# ProPrj_Syntheseproject_2025-2026_2025-11.net
KiCad netlist of a schematic drawn in EasyEDA Pro
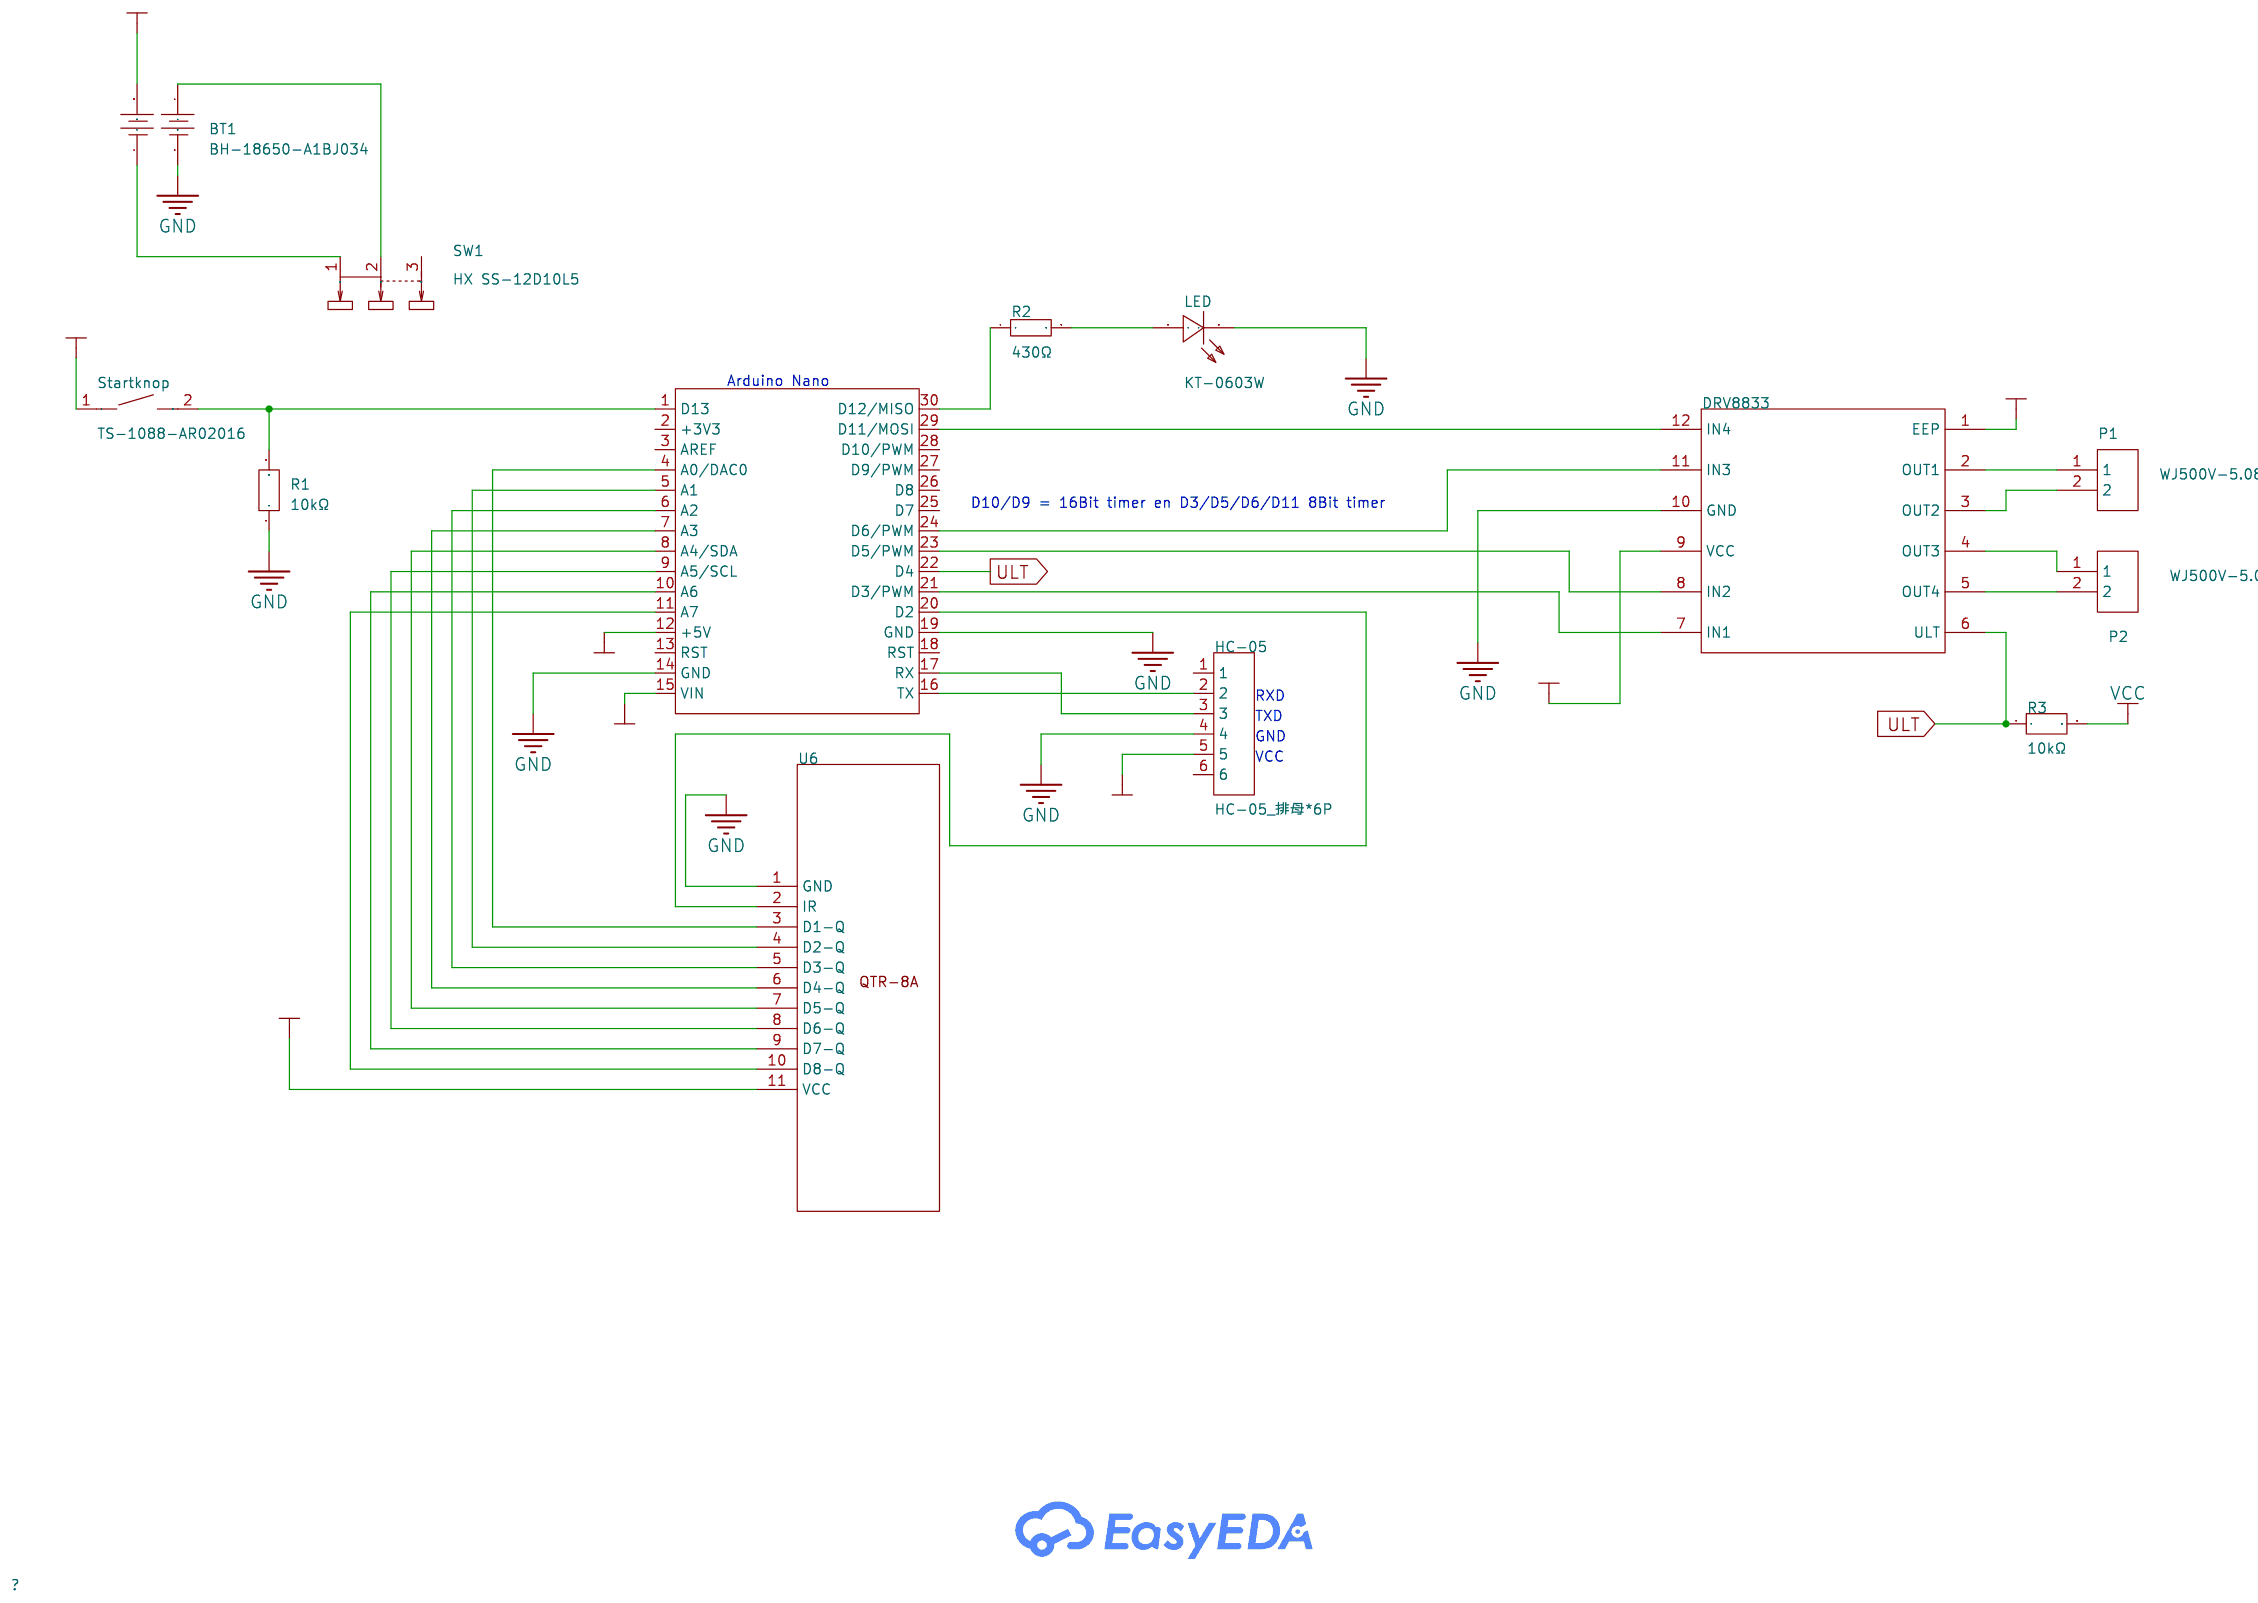
[diagram p0: Totaal]
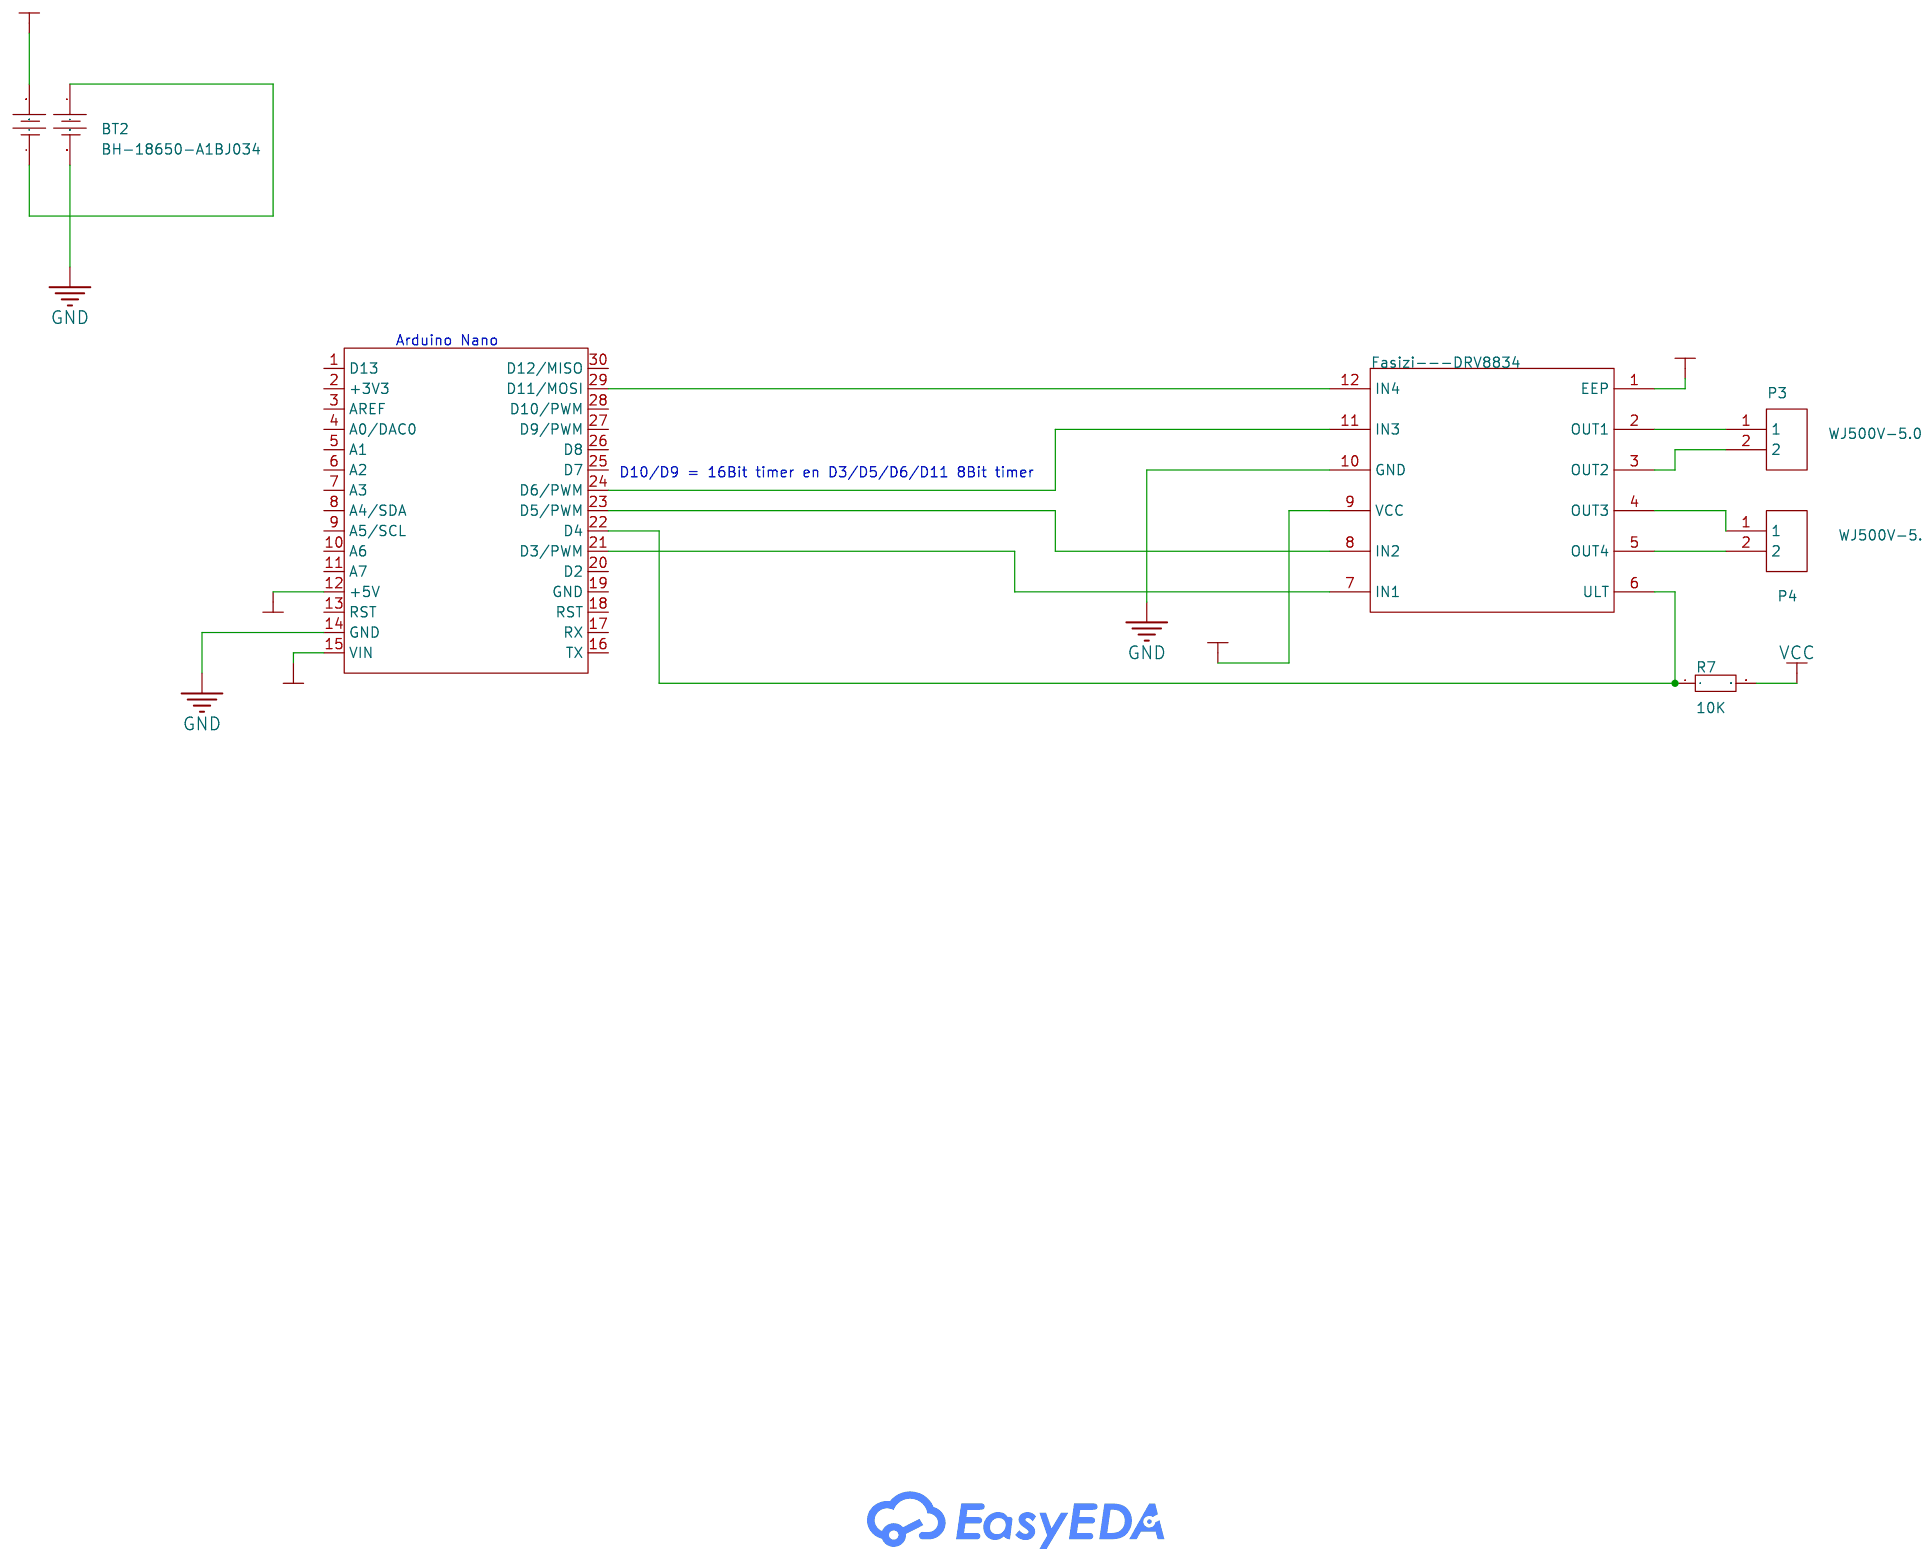
[diagram p1: Deelschema-Drive]
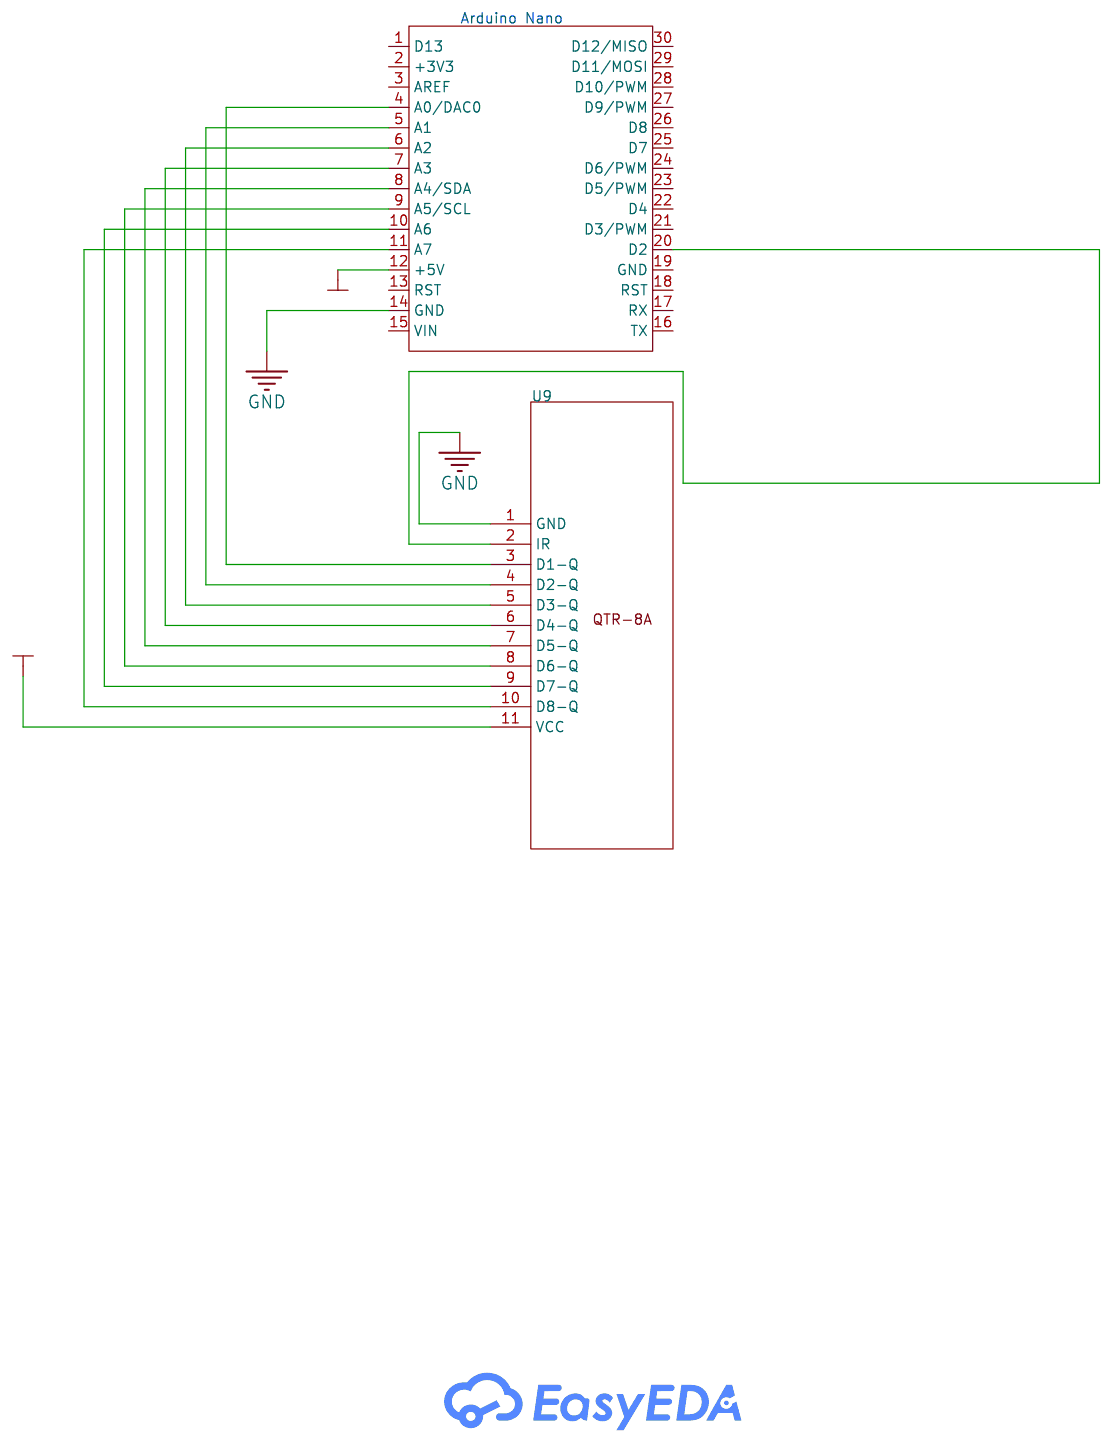
[diagram p2: Deelschema-QTR-8A]
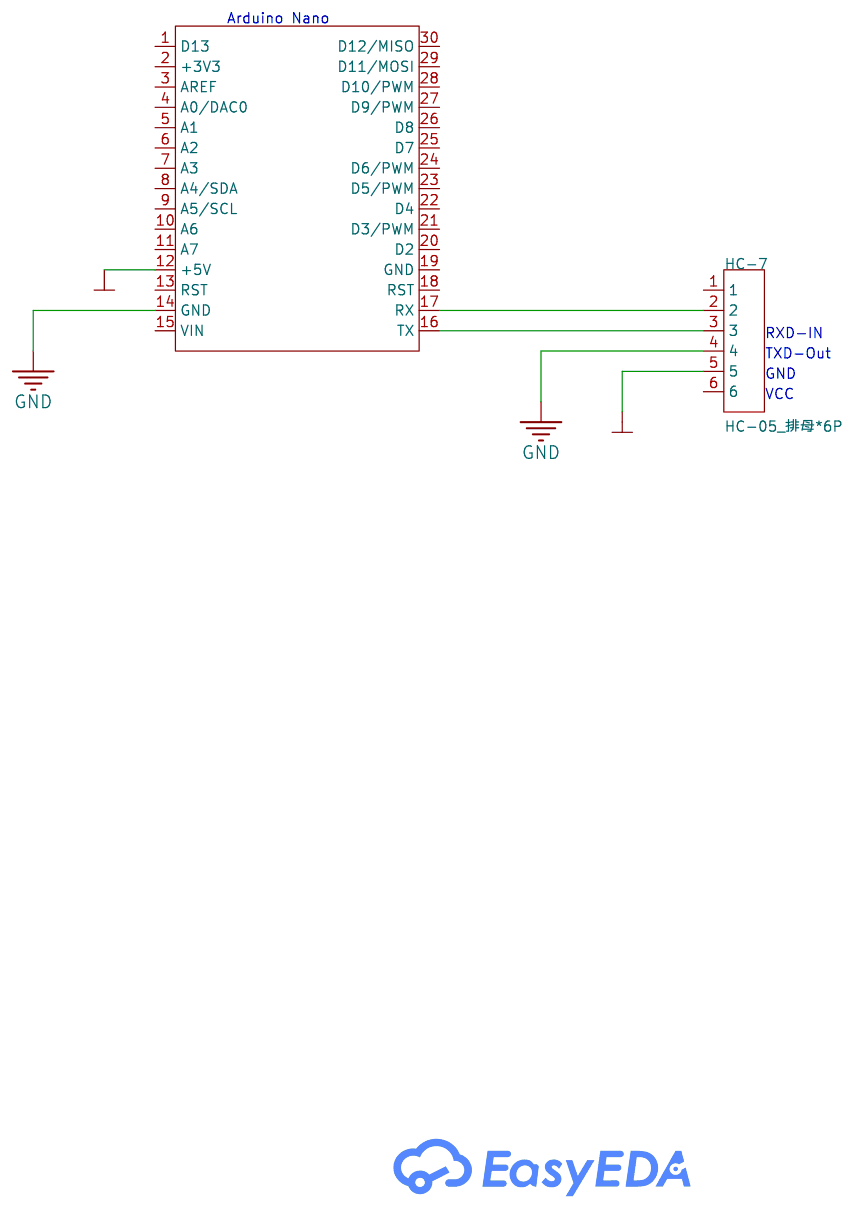
[diagram p3: Deelschema-HC05]
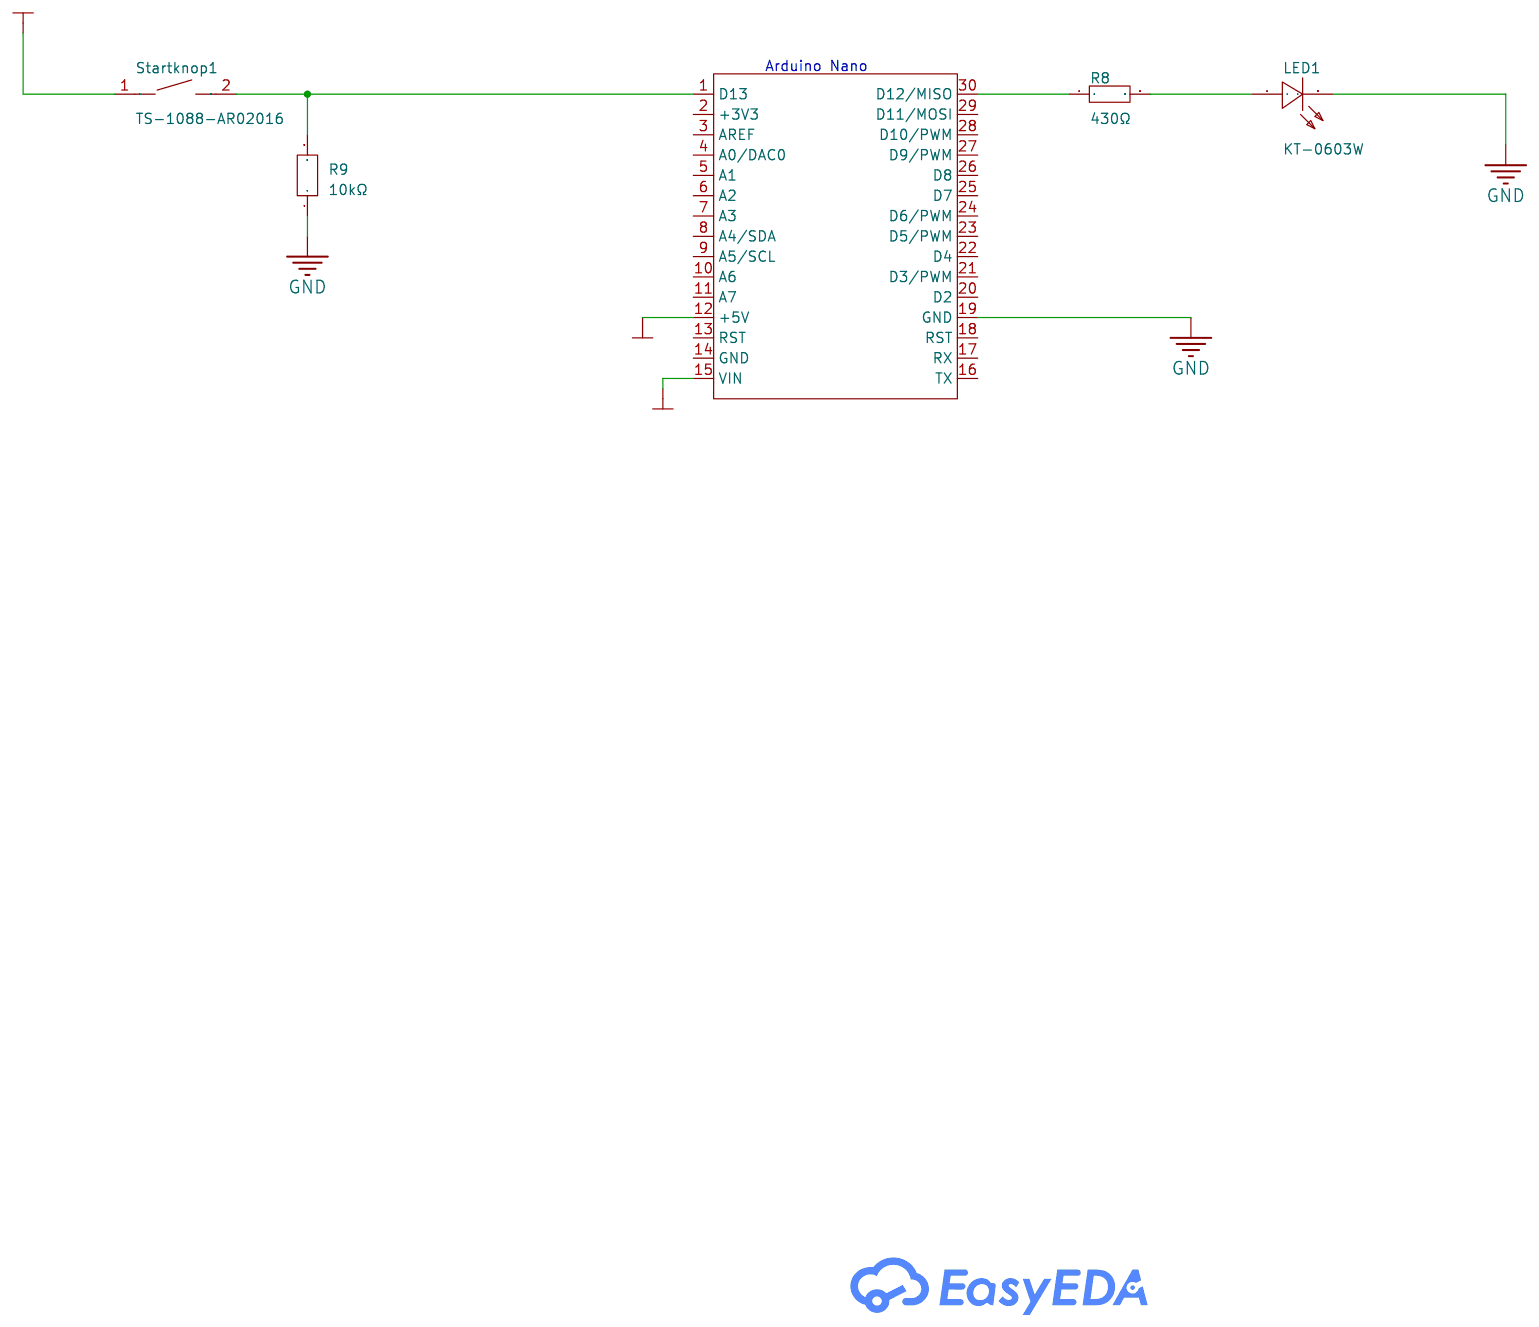
[diagram p4: Deelschema-intterupt]

(export (version "E")
  (design (tool "Eeschema 10.0.6"))
  (components
    (comp (ref "BT1")
      (value "BH-18650-A1BJ034")
      (footprint "easyedapro:BAT-TH_BH-18650-A1BJ034")
      (fields (field (name "Manufacturer") "MYOUNG(美阳)"))
      (libsource (lib "easyedapro") (part "BH-18650-A1BJ034"))
    )
    (comp (ref "DRV8833")
      (value "~")
      (footprint "easyedapro:DRV8833")
      (libsource (lib "easyedapro") (part "DRV8833"))
    )
    (comp (ref "HC-05")
      (value "HC-05_排母*6P")
      (footprint "easyedapro:HDR-TH_6P-P2.50-V-F-R1-C6")
      (libsource (lib "easyedapro") (part "HC-05-*6P"))
    )
    (comp (ref "LED")
      (value "KT-0603W")
      (footprint "easyedapro:LED0603-R-RD_WHITE")
      (fields (field (name "Manufacturer") "KENTO"))
      (libsource (lib "easyedapro") (part "0603White light_C2290"))
    )
    (comp (ref "P1")
      (value "WJ500V-5.08-2P")
      (footprint "easyedapro:CONN-TH_2P-P5.00_WJ500V-5.08-2P")
      (fields (field (name "Manufacturer") "KANGNEX(康奈克斯电气)"))
      (libsource (lib "easyedapro") (part "WJ500V-5.08-2P-14-00A"))
    )
    (comp (ref "P2")
      (value "WJ500V-5.08-2P")
      (footprint "easyedapro:CONN-TH_2P-P5.00_WJ500V-5.08-2P")
      (fields (field (name "Manufacturer") "KANGNEX(康奈克斯电气)"))
      (libsource (lib "easyedapro") (part "WJ500V-5.08-2P-14-00A"))
    )
    (comp (ref "R1")
      (value "10kΩ")
      (footprint "easyedapro:RES-TH_BD2.7-L6.2-P10.20-D0.4")
      (fields (field (name "Manufacturer Part") "MF1/4W-10K±1%-ST52") (field (name "Manufacturer") "VO(翔胜)"))
      (libsource (lib "easyedapro") (part "MF1/4W-10K±1%-ST52"))
    )
    (comp (ref "R2")
      (value "430Ω")
      (footprint "easyedapro:RES-TH_BD1.8-L3.2-P7.20-D0.4")
      (fields (field (name "Manufacturer Part") "MF1/8W-430Ω±1% T") (field (name "Manufacturer") "CCO(千志电子)"))
      (libsource (lib "easyedapro") (part "MF1/8W-430Ω±1% T52"))
    )
    (comp (ref "R3")
      (value "10kΩ")
      (footprint "easyedapro:RES-TH_BD2.7-L6.2-P10.20-D0.4")
      (fields (field (name "Manufacturer Part") "MF1/4W-10K±1%-ST52") (field (name "Manufacturer") "VO(翔胜)"))
      (libsource (lib "easyedapro") (part "MF1/4W-10K±1%-ST52"))
    )
    (comp (ref "Startknop")
      (value "TS-1088-AR02016")
      (footprint "easyedapro:SW-SMD_L3.9-W3.0-P4.45")
      (fields (field (name "Manufacturer") "XUNPU(讯普)"))
      (libsource (lib "easyedapro") (part "TS-1088-AR02016"))
    )
    (comp (ref "SW1")
      (value "HX SS-12D10L5")
      (footprint "easyedapro:SW-TH_HX-SS-12D10L5")
      (fields (field (name "Manufacturer") "hanxia(韩下)"))
      (libsource (lib "easyedapro") (part "HX SS-12D10L5"))
    )
    (comp (ref "U1")
      (value "ABX00028")
      (footprint "easyedapro:MOD-TH_ABX00028")
      (fields (field (name "Manufacturer") "arduino"))
      (libsource (lib "easyedapro") (part "ABX00028"))
    )
    (comp (ref "U6")
      (value "~")
      (footprint "easyedapro:QTR 8A HYS301")
      (libsource (lib "easyedapro") (part "QTR 8A HYS301"))
    )
    (comp (ref "BT2")
      (value "BH-18650-A1BJ034")
      (footprint "easyedapro:BAT-TH_BH-18650-A1BJ034")
      (fields (field (name "Manufacturer") "MYOUNG(美阳)"))
      (libsource (lib "easyedapro") (part "BH-18650-A1BJ034"))
    )
    (comp (ref "Fasizi---DRV8834")
      (value "~")
      (footprint "easyedapro:DRV8833")
      (libsource (lib "easyedapro") (part "DRV8833"))
    )
    (comp (ref "P3")
      (value "WJ500V-5.08-2P")
      (footprint "easyedapro:CONN-TH_2P-P5.00_WJ500V-5.08-2P")
      (fields (field (name "Manufacturer") "KANGNEX(康奈克斯电气)"))
      (libsource (lib "easyedapro") (part "WJ500V-5.08-2P-14-00A"))
    )
    (comp (ref "P4")
      (value "WJ500V-5.08-2P")
      (footprint "easyedapro:CONN-TH_2P-P5.00_WJ500V-5.08-2P")
      (fields (field (name "Manufacturer") "KANGNEX(康奈克斯电气)"))
      (libsource (lib "easyedapro") (part "WJ500V-5.08-2P-14-00A"))
    )
    (comp (ref "R7") (value "10K") (footprint "easyedapro:R0603") (libsource (lib "easyedapro") (part "Res")))
    (comp (ref "U7")
      (value "ABX00028")
      (footprint "easyedapro:MOD-TH_ABX00028")
      (fields (field (name "Manufacturer") "arduino"))
      (libsource (lib "easyedapro") (part "ABX00028"))
    )
    (comp (ref "U8")
      (value "ABX00028")
      (footprint "easyedapro:MOD-TH_ABX00028")
      (fields (field (name "Manufacturer") "arduino"))
      (libsource (lib "easyedapro") (part "ABX00028"))
    )
    (comp (ref "U9")
      (value "~")
      (footprint "easyedapro:QTR 8A HYS301")
      (libsource (lib "easyedapro") (part "QTR 8A HYS301"))
    )
    (comp (ref "HC-7")
      (value "HC-05_排母*6P")
      (footprint "easyedapro:HDR-TH_6P-P2.50-V-F-R1-C6")
      (libsource (lib "easyedapro") (part "HC-05-*6P"))
    )
    (comp (ref "U10")
      (value "ABX00028")
      (footprint "easyedapro:MOD-TH_ABX00028")
      (fields (field (name "Manufacturer") "arduino"))
      (libsource (lib "easyedapro") (part "ABX00028"))
    )
    (comp (ref "LED1")
      (value "KT-0603W")
      (footprint "easyedapro:LED0603-R-RD_WHITE")
      (fields (field (name "Manufacturer") "KENTO"))
      (libsource (lib "easyedapro") (part "0603White light_C2290"))
    )
    (comp (ref "R8")
      (value "430Ω")
      (footprint "easyedapro:RES-TH_BD1.8-L3.2-P7.20-D0.4")
      (fields (field (name "Manufacturer Part") "MF1/8W-430Ω±1% T") (field (name "Manufacturer") "CCO(千志电子)"))
      (libsource (lib "easyedapro") (part "MF1/8W-430Ω±1% T52"))
    )
    (comp (ref "R9")
      (value "10kΩ")
      (footprint "easyedapro:RES-TH_BD2.7-L6.2-P10.20-D0.4")
      (fields (field (name "Manufacturer Part") "MF1/4W-10K±1%-ST52") (field (name "Manufacturer") "VO(翔胜)"))
      (libsource (lib "easyedapro") (part "MF1/4W-10K±1%-ST52"))
    )
    (comp (ref "Startknop1")
      (value "TS-1088-AR02016")
      (footprint "easyedapro:SW-SMD_L3.9-W3.0-P4.45")
      (fields (field (name "Manufacturer") "XUNPU(讯普)"))
      (libsource (lib "easyedapro") (part "TS-1088-AR02016"))
    )
    (comp (ref "U11")
      (value "ABX00028")
      (footprint "easyedapro:MOD-TH_ABX00028")
      (fields (field (name "Manufacturer") "arduino"))
      (libsource (lib "easyedapro") (part "ABX00028"))
    )
  )
  (nets
    (net (code "1") (name "GND") (class "Default")
      (node (ref "BT1") (pin "2") (pinfunction "2_2") (pintype "input"))
      (node (ref "BT2") (pin "2") (pinfunction "2_2") (pintype "input"))
      (node (ref "DRV8833") (pin "10") (pinfunction "GND_10") (pintype "input"))
      (node (ref "Fasizi---DRV8834") (pin "10") (pinfunction "GND_10") (pintype "input"))
      (node (ref "HC-05") (pin "4") (pinfunction "4_4") (pintype "unspecified"))
      (node (ref "HC-7") (pin "4") (pinfunction "4_4") (pintype "unspecified"))
      (node (ref "LED") (pin "2") (pinfunction "K_2") (pintype "unspecified"))
      (node (ref "LED1") (pin "2") (pinfunction "K_2") (pintype "unspecified"))
      (node (ref "R1") (pin "1") (pinfunction "1_1") (pintype "unspecified"))
      (node (ref "R9") (pin "1") (pinfunction "1_1") (pintype "unspecified"))
      (node (ref "U1") (pin "14") (pinfunction "GND_14") (pintype "unspecified"))
      (node (ref "U1") (pin "19") (pinfunction "GND_19") (pintype "unspecified"))
      (node (ref "U10") (pin "14") (pinfunction "GND_14") (pintype "unspecified"))
      (node (ref "U11") (pin "19") (pinfunction "GND_19") (pintype "unspecified"))
      (node (ref "U6") (pin "1") (pinfunction "GND_1") (pintype "input"))
      (node (ref "U7") (pin "14") (pinfunction "GND_14") (pintype "unspecified"))
      (node (ref "U8") (pin "14") (pinfunction "GND_14") (pintype "unspecified"))
      (node (ref "U9") (pin "1") (pinfunction "GND_1") (pintype "input"))
    )
    (net (code "2") (name "Net-(BT1-Pad1)") (class "Default")
      (node (ref "BT1") (pin "1") (pinfunction "1_1") (pintype "input"))
      (node (ref "SW1") (pin "2") (pinfunction "2_2") (pintype "unspecified"))
    )
    (net (code "3") (name "Net-(BT1-Pad4)") (class "Default")
      (node (ref "BT1") (pin "4") (pinfunction "4_4") (pintype "input"))
      (node (ref "SW1") (pin "1") (pinfunction "1_1") (pintype "unspecified"))
    )
    (net (code "4") (name "Net-(BT2-Pad1)") (class "Default")
      (node (ref "BT2") (pin "1") (pinfunction "1_1") (pintype "input"))
      (node (ref "BT2") (pin "4") (pinfunction "4_4") (pintype "input"))
    )
    (net (code "5") (name "Net-(DRV8833-IN1)") (class "Default")
      (node (ref "DRV8833") (pin "7") (pinfunction "IN1_7") (pintype "input"))
      (node (ref "U1") (pin "21") (pinfunction "D3/PWM_21") (pintype "unspecified"))
    )
    (net (code "6") (name "Net-(DRV8833-IN2)") (class "Default")
      (node (ref "DRV8833") (pin "8") (pinfunction "IN2_8") (pintype "input"))
      (node (ref "U1") (pin "23") (pinfunction "D5/PWM_23") (pintype "unspecified"))
    )
    (net (code "7") (name "Net-(DRV8833-IN3)") (class "Default")
      (node (ref "DRV8833") (pin "11") (pinfunction "IN3_11") (pintype "input"))
      (node (ref "U1") (pin "24") (pinfunction "D6/PWM_24") (pintype "unspecified"))
    )
    (net (code "8") (name "Net-(DRV8833-IN4)") (class "Default")
      (node (ref "DRV8833") (pin "12") (pinfunction "IN4_12") (pintype "input"))
      (node (ref "U1") (pin "29") (pinfunction "D11/MOSI_29") (pintype "unspecified"))
    )
    (net (code "9") (name "Net-(DRV8833-OUT1)") (class "Default")
      (node (ref "DRV8833") (pin "2") (pinfunction "OUT1_2") (pintype "input"))
      (node (ref "P1") (pin "1") (pinfunction "1_1") (pintype "unspecified"))
    )
    (net (code "10") (name "Net-(DRV8833-OUT2)") (class "Default")
      (node (ref "DRV8833") (pin "3") (pinfunction "OUT2_3") (pintype "input"))
      (node (ref "P1") (pin "2") (pinfunction "2_2") (pintype "unspecified"))
    )
    (net (code "11") (name "Net-(DRV8833-OUT3)") (class "Default")
      (node (ref "DRV8833") (pin "4") (pinfunction "OUT3_4") (pintype "input"))
      (node (ref "P2") (pin "1") (pinfunction "1_1") (pintype "unspecified"))
    )
    (net (code "12") (name "Net-(DRV8833-OUT4)") (class "Default")
      (node (ref "DRV8833") (pin "5") (pinfunction "OUT4_5") (pintype "input"))
      (node (ref "P2") (pin "2") (pinfunction "2_2") (pintype "unspecified"))
    )
    (net (code "13") (name "Net-(Fasizi---DRV8834-IN1)") (class "Default")
      (node (ref "Fasizi---DRV8834") (pin "7") (pinfunction "IN1_7") (pintype "input"))
      (node (ref "U7") (pin "21") (pinfunction "D3/PWM_21") (pintype "unspecified"))
    )
    (net (code "14") (name "Net-(Fasizi---DRV8834-IN2)") (class "Default")
      (node (ref "Fasizi---DRV8834") (pin "8") (pinfunction "IN2_8") (pintype "input"))
      (node (ref "U7") (pin "23") (pinfunction "D5/PWM_23") (pintype "unspecified"))
    )
    (net (code "15") (name "Net-(Fasizi---DRV8834-IN3)") (class "Default")
      (node (ref "Fasizi---DRV8834") (pin "11") (pinfunction "IN3_11") (pintype "input"))
      (node (ref "U7") (pin "24") (pinfunction "D6/PWM_24") (pintype "unspecified"))
    )
    (net (code "16") (name "Net-(Fasizi---DRV8834-IN4)") (class "Default")
      (node (ref "Fasizi---DRV8834") (pin "12") (pinfunction "IN4_12") (pintype "input"))
      (node (ref "U7") (pin "29") (pinfunction "D11/MOSI_29") (pintype "unspecified"))
    )
    (net (code "17") (name "Net-(Fasizi---DRV8834-OUT1)") (class "Default")
      (node (ref "Fasizi---DRV8834") (pin "2") (pinfunction "OUT1_2") (pintype "input"))
      (node (ref "P3") (pin "1") (pinfunction "1_1") (pintype "unspecified"))
    )
    (net (code "18") (name "Net-(Fasizi---DRV8834-OUT2)") (class "Default")
      (node (ref "Fasizi---DRV8834") (pin "3") (pinfunction "OUT2_3") (pintype "input"))
      (node (ref "P3") (pin "2") (pinfunction "2_2") (pintype "unspecified"))
    )
    (net (code "19") (name "Net-(Fasizi---DRV8834-OUT3)") (class "Default")
      (node (ref "Fasizi---DRV8834") (pin "4") (pinfunction "OUT3_4") (pintype "input"))
      (node (ref "P4") (pin "1") (pinfunction "1_1") (pintype "unspecified"))
    )
    (net (code "20") (name "Net-(Fasizi---DRV8834-OUT4)") (class "Default")
      (node (ref "Fasizi---DRV8834") (pin "5") (pinfunction "OUT4_5") (pintype "input"))
      (node (ref "P4") (pin "2") (pinfunction "2_2") (pintype "unspecified"))
    )
    (net (code "21") (name "Net-(Fasizi---DRV8834-ULT)") (class "Default")
      (node (ref "Fasizi---DRV8834") (pin "6") (pinfunction "ULT_6") (pintype "input"))
      (node (ref "R7") (pin "1") (pinfunction "1_1") (pintype "input"))
      (node (ref "U7") (pin "22") (pinfunction "D4_22") (pintype "unspecified"))
    )
    (net (code "22") (name "Net-(LED-A)") (class "Default")
      (node (ref "LED") (pin "1") (pinfunction "A_1") (pintype "unspecified"))
      (node (ref "R2") (pin "2") (pinfunction "2_2") (pintype "unspecified"))
    )
    (net (code "23") (name "Net-(LED1-A)") (class "Default")
      (node (ref "LED1") (pin "1") (pinfunction "A_1") (pintype "unspecified"))
      (node (ref "R8") (pin "2") (pinfunction "2_2") (pintype "unspecified"))
    )
    (net (code "24") (name "Net-(U1-A0{slash}DAC0)") (class "Default")
      (node (ref "U1") (pin "4") (pinfunction "A0/DAC0_4") (pintype "unspecified"))
      (node (ref "U6") (pin "3") (pinfunction "D1-Q_3") (pintype "output"))
    )
    (net (code "25") (name "Net-(U1-A1)") (class "Default")
      (node (ref "U1") (pin "5") (pinfunction "A1_5") (pintype "unspecified"))
      (node (ref "U6") (pin "4") (pinfunction "D2-Q_4") (pintype "output"))
    )
    (net (code "26") (name "Net-(U1-A2)") (class "Default")
      (node (ref "U1") (pin "6") (pinfunction "A2_6") (pintype "unspecified"))
      (node (ref "U6") (pin "5") (pinfunction "D3-Q_5") (pintype "output"))
    )
    (net (code "27") (name "Net-(U1-A3)") (class "Default")
      (node (ref "U1") (pin "7") (pinfunction "A3_7") (pintype "unspecified"))
      (node (ref "U6") (pin "6") (pinfunction "D4-Q_6") (pintype "output"))
    )
    (net (code "28") (name "Net-(U1-A4{slash}SDA)") (class "Default")
      (node (ref "U1") (pin "8") (pinfunction "A4/SDA_8") (pintype "unspecified"))
      (node (ref "U6") (pin "7") (pinfunction "D5-Q_7") (pintype "output"))
    )
    (net (code "29") (name "Net-(U1-A5{slash}SCL)") (class "Default")
      (node (ref "U1") (pin "9") (pinfunction "A5/SCL_9") (pintype "unspecified"))
      (node (ref "U6") (pin "8") (pinfunction "D6-Q_8") (pintype "output"))
    )
    (net (code "30") (name "Net-(U1-A6)") (class "Default")
      (node (ref "U1") (pin "10") (pinfunction "A6_10") (pintype "unspecified"))
      (node (ref "U6") (pin "9") (pinfunction "D7-Q_9") (pintype "output"))
    )
    (net (code "31") (name "Net-(U1-A7)") (class "Default")
      (node (ref "U1") (pin "11") (pinfunction "A7_11") (pintype "unspecified"))
      (node (ref "U6") (pin "10") (pinfunction "D8-Q_10") (pintype "output"))
    )
    (net (code "32") (name "Net-(U1-D2)") (class "Default")
      (node (ref "U1") (pin "20") (pinfunction "D2_20") (pintype "unspecified"))
      (node (ref "U6") (pin "2") (pinfunction "IR_2") (pintype "input"))
    )
    (net (code "33") (name "Net-(U1-D12{slash}MISO)") (class "Default")
      (node (ref "R2") (pin "1") (pinfunction "1_1") (pintype "unspecified"))
      (node (ref "U1") (pin "30") (pinfunction "D12/MISO_30") (pintype "unspecified"))
    )
    (net (code "34") (name "Net-(U1-D13)") (class "Default")
      (node (ref "R1") (pin "2") (pinfunction "2_2") (pintype "unspecified"))
      (node (ref "Startknop") (pin "2") (pinfunction "2_2") (pintype "unspecified"))
      (node (ref "U1") (pin "1") (pinfunction "D13_1") (pintype "unspecified"))
    )
    (net (code "35") (name "Net-(U1-RX)") (class "Default")
      (node (ref "HC-05") (pin "3") (pinfunction "3_3") (pintype "unspecified"))
      (node (ref "U1") (pin "17") (pinfunction "RX_17") (pintype "unspecified"))
    )
    (net (code "36") (name "Net-(U1-TX)") (class "Default")
      (node (ref "HC-05") (pin "2") (pinfunction "2_2") (pintype "unspecified"))
      (node (ref "U1") (pin "16") (pinfunction "TX_16") (pintype "unspecified"))
    )
    (net (code "37") (name "Net-(U8-A0{slash}DAC0)") (class "Default")
      (node (ref "U8") (pin "4") (pinfunction "A0/DAC0_4") (pintype "unspecified"))
      (node (ref "U9") (pin "3") (pinfunction "D1-Q_3") (pintype "output"))
    )
    (net (code "38") (name "Net-(U8-A1)") (class "Default")
      (node (ref "U8") (pin "5") (pinfunction "A1_5") (pintype "unspecified"))
      (node (ref "U9") (pin "4") (pinfunction "D2-Q_4") (pintype "output"))
    )
    (net (code "39") (name "Net-(U8-A2)") (class "Default")
      (node (ref "U8") (pin "6") (pinfunction "A2_6") (pintype "unspecified"))
      (node (ref "U9") (pin "5") (pinfunction "D3-Q_5") (pintype "output"))
    )
    (net (code "40") (name "Net-(U8-A3)") (class "Default")
      (node (ref "U8") (pin "7") (pinfunction "A3_7") (pintype "unspecified"))
      (node (ref "U9") (pin "6") (pinfunction "D4-Q_6") (pintype "output"))
    )
    (net (code "41") (name "Net-(U8-A4{slash}SDA)") (class "Default")
      (node (ref "U8") (pin "8") (pinfunction "A4/SDA_8") (pintype "unspecified"))
      (node (ref "U9") (pin "7") (pinfunction "D5-Q_7") (pintype "output"))
    )
    (net (code "42") (name "Net-(U8-A5{slash}SCL)") (class "Default")
      (node (ref "U8") (pin "9") (pinfunction "A5/SCL_9") (pintype "unspecified"))
      (node (ref "U9") (pin "8") (pinfunction "D6-Q_8") (pintype "output"))
    )
    (net (code "43") (name "Net-(U8-A6)") (class "Default")
      (node (ref "U8") (pin "10") (pinfunction "A6_10") (pintype "unspecified"))
      (node (ref "U9") (pin "9") (pinfunction "D7-Q_9") (pintype "output"))
    )
    (net (code "44") (name "Net-(U8-A7)") (class "Default")
      (node (ref "U8") (pin "11") (pinfunction "A7_11") (pintype "unspecified"))
      (node (ref "U9") (pin "10") (pinfunction "D8-Q_10") (pintype "output"))
    )
    (net (code "45") (name "Net-(U8-D2)") (class "Default")
      (node (ref "U8") (pin "20") (pinfunction "D2_20") (pintype "unspecified"))
      (node (ref "U9") (pin "2") (pinfunction "IR_2") (pintype "input"))
    )
    (net (code "46") (name "Net-(U10-RX)") (class "Default")
      (node (ref "HC-7") (pin "2") (pinfunction "2_2") (pintype "unspecified"))
      (node (ref "U10") (pin "17") (pinfunction "RX_17") (pintype "unspecified"))
    )
    (net (code "47") (name "Net-(U10-TX)") (class "Default")
      (node (ref "HC-7") (pin "3") (pinfunction "3_3") (pintype "unspecified"))
      (node (ref "U10") (pin "16") (pinfunction "TX_16") (pintype "unspecified"))
    )
    (net (code "48") (name "Net-(U11-D12{slash}MISO)") (class "Default")
      (node (ref "R8") (pin "1") (pinfunction "1_1") (pintype "unspecified"))
      (node (ref "U11") (pin "30") (pinfunction "D12/MISO_30") (pintype "unspecified"))
    )
    (net (code "49") (name "Net-(U11-D13)") (class "Default")
      (node (ref "R9") (pin "2") (pinfunction "2_2") (pintype "unspecified"))
      (node (ref "Startknop1") (pin "2") (pinfunction "2_2") (pintype "unspecified"))
      (node (ref "U11") (pin "1") (pinfunction "D13_1") (pintype "unspecified"))
    )
    (net (code "50") (name "ULT") (class "Default")
      (node (ref "DRV8833") (pin "6") (pinfunction "ULT_6") (pintype "input"))
      (node (ref "R3") (pin "1") (pinfunction "1_1") (pintype "unspecified"))
      (node (ref "U1") (pin "22") (pinfunction "D4_22") (pintype "unspecified"))
    )
    (net (code "51") (name "VBAT") (class "Default")
      (node (ref "BT1") (pin "3") (pinfunction "3_3") (pintype "input"))
      (node (ref "BT2") (pin "3") (pinfunction "3_3") (pintype "input"))
      (node (ref "DRV8833") (pin "9") (pinfunction "VCC_9") (pintype "input"))
      (node (ref "Fasizi---DRV8834") (pin "9") (pinfunction "VCC_9") (pintype "input"))
      (node (ref "U1") (pin "15") (pinfunction "VIN_15") (pintype "unspecified"))
      (node (ref "U11") (pin "15") (pinfunction "VIN_15") (pintype "unspecified"))
      (node (ref "U7") (pin "15") (pinfunction "VIN_15") (pintype "unspecified"))
    )
    (net (code "52") (name "VCC") (class "Default")
      (node (ref "DRV8833") (pin "1") (pinfunction "EEP_1") (pintype "input"))
      (node (ref "Fasizi---DRV8834") (pin "1") (pinfunction "EEP_1") (pintype "input"))
      (node (ref "HC-05") (pin "5") (pinfunction "5_5") (pintype "unspecified"))
      (node (ref "HC-7") (pin "5") (pinfunction "5_5") (pintype "unspecified"))
      (node (ref "R3") (pin "2") (pinfunction "2_2") (pintype "unspecified"))
      (node (ref "R7") (pin "2") (pinfunction "2_2") (pintype "input"))
      (node (ref "Startknop") (pin "1") (pinfunction "1_1") (pintype "unspecified"))
      (node (ref "Startknop1") (pin "1") (pinfunction "1_1") (pintype "unspecified"))
      (node (ref "U1") (pin "12") (pinfunction "+5V_12") (pintype "unspecified"))
      (node (ref "U10") (pin "12") (pinfunction "+5V_12") (pintype "unspecified"))
      (node (ref "U11") (pin "12") (pinfunction "+5V_12") (pintype "unspecified"))
      (node (ref "U6") (pin "11") (pinfunction "VCC_11") (pintype "input"))
      (node (ref "U7") (pin "12") (pinfunction "+5V_12") (pintype "unspecified"))
      (node (ref "U8") (pin "12") (pinfunction "+5V_12") (pintype "unspecified"))
      (node (ref "U9") (pin "11") (pinfunction "VCC_11") (pintype "input"))
    )
    (net (code "53") (name "unconnected-(HC-05-Pad1)") (class "Default")
      (node (ref "HC-05") (pin "1") (pinfunction "1_1") (pintype "unspecified"))
    )
    (net (code "54") (name "unconnected-(HC-05-Pad6)") (class "Default")
      (node (ref "HC-05") (pin "6") (pinfunction "6_6") (pintype "unspecified"))
    )
    (net (code "55") (name "unconnected-(HC-7-Pad1)") (class "Default")
      (node (ref "HC-7") (pin "1") (pinfunction "1_1") (pintype "unspecified"))
    )
    (net (code "56") (name "unconnected-(HC-7-Pad6)") (class "Default")
      (node (ref "HC-7") (pin "6") (pinfunction "6_6") (pintype "unspecified"))
    )
    (net (code "57") (name "unconnected-(SW1-Pad3)") (class "Default")
      (node (ref "SW1") (pin "3") (pinfunction "3_3") (pintype "unspecified"))
    )
    (net (code "58") (name "unconnected-(U1-+3V3-Pad2)") (class "Default")
      (node (ref "U1") (pin "2") (pinfunction "+3V3_2") (pintype "unspecified"))
    )
    (net (code "59") (name "unconnected-(U1-AREF-Pad3)") (class "Default")
      (node (ref "U1") (pin "3") (pinfunction "AREF_3") (pintype "unspecified"))
    )
    (net (code "60") (name "unconnected-(U1-D7-Pad25)") (class "Default")
      (node (ref "U1") (pin "25") (pinfunction "D7_25") (pintype "unspecified"))
    )
    (net (code "61") (name "unconnected-(U1-D8-Pad26)") (class "Default")
      (node (ref "U1") (pin "26") (pinfunction "D8_26") (pintype "unspecified"))
    )
    (net (code "62") (name "unconnected-(U1-D9{slash}PWM-Pad27)") (class "Default")
      (node (ref "U1") (pin "27") (pinfunction "D9/PWM_27") (pintype "unspecified"))
    )
    (net (code "63") (name "unconnected-(U1-D10{slash}PWM-Pad28)") (class "Default")
      (node (ref "U1") (pin "28") (pinfunction "D10/PWM_28") (pintype "unspecified"))
    )
    (net (code "64") (name "unconnected-(U1-RST-Pad13)") (class "Default")
      (node (ref "U1") (pin "13") (pinfunction "RST_13") (pintype "unspecified"))
    )
    (net (code "65") (name "unconnected-(U1-RST-Pad18)") (class "Default")
      (node (ref "U1") (pin "18") (pinfunction "RST_18") (pintype "unspecified"))
    )
    (net (code "66") (name "unconnected-(U7-+3V3-Pad2)") (class "Default")
      (node (ref "U7") (pin "2") (pinfunction "+3V3_2") (pintype "unspecified"))
    )
    (net (code "67") (name "unconnected-(U7-A0{slash}DAC0-Pad4)") (class "Default")
      (node (ref "U7") (pin "4") (pinfunction "A0/DAC0_4") (pintype "unspecified"))
    )
    (net (code "68") (name "unconnected-(U7-A1-Pad5)") (class "Default")
      (node (ref "U7") (pin "5") (pinfunction "A1_5") (pintype "unspecified"))
    )
    (net (code "69") (name "unconnected-(U7-A2-Pad6)") (class "Default")
      (node (ref "U7") (pin "6") (pinfunction "A2_6") (pintype "unspecified"))
    )
    (net (code "70") (name "unconnected-(U7-A3-Pad7)") (class "Default")
      (node (ref "U7") (pin "7") (pinfunction "A3_7") (pintype "unspecified"))
    )
    (net (code "71") (name "unconnected-(U7-A4{slash}SDA-Pad8)") (class "Default")
      (node (ref "U7") (pin "8") (pinfunction "A4/SDA_8") (pintype "unspecified"))
    )
    (net (code "72") (name "unconnected-(U7-A5{slash}SCL-Pad9)") (class "Default")
      (node (ref "U7") (pin "9") (pinfunction "A5/SCL_9") (pintype "unspecified"))
    )
    (net (code "73") (name "unconnected-(U7-A6-Pad10)") (class "Default")
      (node (ref "U7") (pin "10") (pinfunction "A6_10") (pintype "unspecified"))
    )
    (net (code "74") (name "unconnected-(U7-A7-Pad11)") (class "Default")
      (node (ref "U7") (pin "11") (pinfunction "A7_11") (pintype "unspecified"))
    )
    (net (code "75") (name "unconnected-(U7-AREF-Pad3)") (class "Default")
      (node (ref "U7") (pin "3") (pinfunction "AREF_3") (pintype "unspecified"))
    )
    (net (code "76") (name "unconnected-(U7-D2-Pad20)") (class "Default")
      (node (ref "U7") (pin "20") (pinfunction "D2_20") (pintype "unspecified"))
    )
    (net (code "77") (name "unconnected-(U7-D7-Pad25)") (class "Default")
      (node (ref "U7") (pin "25") (pinfunction "D7_25") (pintype "unspecified"))
    )
    (net (code "78") (name "unconnected-(U7-D8-Pad26)") (class "Default")
      (node (ref "U7") (pin "26") (pinfunction "D8_26") (pintype "unspecified"))
    )
    (net (code "79") (name "unconnected-(U7-D9{slash}PWM-Pad27)") (class "Default")
      (node (ref "U7") (pin "27") (pinfunction "D9/PWM_27") (pintype "unspecified"))
    )
    (net (code "80") (name "unconnected-(U7-D10{slash}PWM-Pad28)") (class "Default")
      (node (ref "U7") (pin "28") (pinfunction "D10/PWM_28") (pintype "unspecified"))
    )
    (net (code "81") (name "unconnected-(U7-D12{slash}MISO-Pad30)") (class "Default")
      (node (ref "U7") (pin "30") (pinfunction "D12/MISO_30") (pintype "unspecified"))
    )
    (net (code "82") (name "unconnected-(U7-D13-Pad1)") (class "Default")
      (node (ref "U7") (pin "1") (pinfunction "D13_1") (pintype "unspecified"))
    )
    (net (code "83") (name "unconnected-(U7-GND-Pad19)") (class "Default")
      (node (ref "U7") (pin "19") (pinfunction "GND_19") (pintype "unspecified"))
    )
    (net (code "84") (name "unconnected-(U7-RST-Pad13)") (class "Default")
      (node (ref "U7") (pin "13") (pinfunction "RST_13") (pintype "unspecified"))
    )
    (net (code "85") (name "unconnected-(U7-RST-Pad18)") (class "Default")
      (node (ref "U7") (pin "18") (pinfunction "RST_18") (pintype "unspecified"))
    )
    (net (code "86") (name "unconnected-(U7-RX-Pad17)") (class "Default")
      (node (ref "U7") (pin "17") (pinfunction "RX_17") (pintype "unspecified"))
    )
    (net (code "87") (name "unconnected-(U7-TX-Pad16)") (class "Default")
      (node (ref "U7") (pin "16") (pinfunction "TX_16") (pintype "unspecified"))
    )
    (net (code "88") (name "unconnected-(U8-+3V3-Pad2)") (class "Default")
      (node (ref "U8") (pin "2") (pinfunction "+3V3_2") (pintype "unspecified"))
    )
    (net (code "89") (name "unconnected-(U8-AREF-Pad3)") (class "Default")
      (node (ref "U8") (pin "3") (pinfunction "AREF_3") (pintype "unspecified"))
    )
    (net (code "90") (name "unconnected-(U8-D3{slash}PWM-Pad21)") (class "Default")
      (node (ref "U8") (pin "21") (pinfunction "D3/PWM_21") (pintype "unspecified"))
    )
    (net (code "91") (name "unconnected-(U8-D4-Pad22)") (class "Default")
      (node (ref "U8") (pin "22") (pinfunction "D4_22") (pintype "unspecified"))
    )
    (net (code "92") (name "unconnected-(U8-D5{slash}PWM-Pad23)") (class "Default")
      (node (ref "U8") (pin "23") (pinfunction "D5/PWM_23") (pintype "unspecified"))
    )
    (net (code "93") (name "unconnected-(U8-D6{slash}PWM-Pad24)") (class "Default")
      (node (ref "U8") (pin "24") (pinfunction "D6/PWM_24") (pintype "unspecified"))
    )
    (net (code "94") (name "unconnected-(U8-D7-Pad25)") (class "Default")
      (node (ref "U8") (pin "25") (pinfunction "D7_25") (pintype "unspecified"))
    )
    (net (code "95") (name "unconnected-(U8-D8-Pad26)") (class "Default")
      (node (ref "U8") (pin "26") (pinfunction "D8_26") (pintype "unspecified"))
    )
    (net (code "96") (name "unconnected-(U8-D9{slash}PWM-Pad27)") (class "Default")
      (node (ref "U8") (pin "27") (pinfunction "D9/PWM_27") (pintype "unspecified"))
    )
    (net (code "97") (name "unconnected-(U8-D10{slash}PWM-Pad28)") (class "Default")
      (node (ref "U8") (pin "28") (pinfunction "D10/PWM_28") (pintype "unspecified"))
    )
    (net (code "98") (name "unconnected-(U8-D11{slash}MOSI-Pad29)") (class "Default")
      (node (ref "U8") (pin "29") (pinfunction "D11/MOSI_29") (pintype "unspecified"))
    )
    (net (code "99") (name "unconnected-(U8-D12{slash}MISO-Pad30)") (class "Default")
      (node (ref "U8") (pin "30") (pinfunction "D12/MISO_30") (pintype "unspecified"))
    )
    (net (code "100") (name "unconnected-(U8-D13-Pad1)") (class "Default")
      (node (ref "U8") (pin "1") (pinfunction "D13_1") (pintype "unspecified"))
    )
    (net (code "101") (name "unconnected-(U8-GND-Pad19)") (class "Default")
      (node (ref "U8") (pin "19") (pinfunction "GND_19") (pintype "unspecified"))
    )
    (net (code "102") (name "unconnected-(U8-RST-Pad13)") (class "Default")
      (node (ref "U8") (pin "13") (pinfunction "RST_13") (pintype "unspecified"))
    )
    (net (code "103") (name "unconnected-(U8-RST-Pad18)") (class "Default")
      (node (ref "U8") (pin "18") (pinfunction "RST_18") (pintype "unspecified"))
    )
    (net (code "104") (name "unconnected-(U8-RX-Pad17)") (class "Default")
      (node (ref "U8") (pin "17") (pinfunction "RX_17") (pintype "unspecified"))
    )
    (net (code "105") (name "unconnected-(U8-TX-Pad16)") (class "Default")
      (node (ref "U8") (pin "16") (pinfunction "TX_16") (pintype "unspecified"))
    )
    (net (code "106") (name "unconnected-(U8-VIN-Pad15)") (class "Default")
      (node (ref "U8") (pin "15") (pinfunction "VIN_15") (pintype "unspecified"))
    )
    (net (code "107") (name "unconnected-(U10-+3V3-Pad2)") (class "Default")
      (node (ref "U10") (pin "2") (pinfunction "+3V3_2") (pintype "unspecified"))
    )
    (net (code "108") (name "unconnected-(U10-A0{slash}DAC0-Pad4)") (class "Default")
      (node (ref "U10") (pin "4") (pinfunction "A0/DAC0_4") (pintype "unspecified"))
    )
    (net (code "109") (name "unconnected-(U10-A1-Pad5)") (class "Default")
      (node (ref "U10") (pin "5") (pinfunction "A1_5") (pintype "unspecified"))
    )
    (net (code "110") (name "unconnected-(U10-A2-Pad6)") (class "Default")
      (node (ref "U10") (pin "6") (pinfunction "A2_6") (pintype "unspecified"))
    )
    (net (code "111") (name "unconnected-(U10-A3-Pad7)") (class "Default")
      (node (ref "U10") (pin "7") (pinfunction "A3_7") (pintype "unspecified"))
    )
    (net (code "112") (name "unconnected-(U10-A4{slash}SDA-Pad8)") (class "Default")
      (node (ref "U10") (pin "8") (pinfunction "A4/SDA_8") (pintype "unspecified"))
    )
    (net (code "113") (name "unconnected-(U10-A5{slash}SCL-Pad9)") (class "Default")
      (node (ref "U10") (pin "9") (pinfunction "A5/SCL_9") (pintype "unspecified"))
    )
    (net (code "114") (name "unconnected-(U10-A6-Pad10)") (class "Default")
      (node (ref "U10") (pin "10") (pinfunction "A6_10") (pintype "unspecified"))
    )
    (net (code "115") (name "unconnected-(U10-A7-Pad11)") (class "Default")
      (node (ref "U10") (pin "11") (pinfunction "A7_11") (pintype "unspecified"))
    )
    (net (code "116") (name "unconnected-(U10-AREF-Pad3)") (class "Default")
      (node (ref "U10") (pin "3") (pinfunction "AREF_3") (pintype "unspecified"))
    )
    (net (code "117") (name "unconnected-(U10-D2-Pad20)") (class "Default")
      (node (ref "U10") (pin "20") (pinfunction "D2_20") (pintype "unspecified"))
    )
    (net (code "118") (name "unconnected-(U10-D3{slash}PWM-Pad21)") (class "Default")
      (node (ref "U10") (pin "21") (pinfunction "D3/PWM_21") (pintype "unspecified"))
    )
    (net (code "119") (name "unconnected-(U10-D4-Pad22)") (class "Default")
      (node (ref "U10") (pin "22") (pinfunction "D4_22") (pintype "unspecified"))
    )
    (net (code "120") (name "unconnected-(U10-D5{slash}PWM-Pad23)") (class "Default")
      (node (ref "U10") (pin "23") (pinfunction "D5/PWM_23") (pintype "unspecified"))
    )
    (net (code "121") (name "unconnected-(U10-D6{slash}PWM-Pad24)") (class "Default")
      (node (ref "U10") (pin "24") (pinfunction "D6/PWM_24") (pintype "unspecified"))
    )
    (net (code "122") (name "unconnected-(U10-D7-Pad25)") (class "Default")
      (node (ref "U10") (pin "25") (pinfunction "D7_25") (pintype "unspecified"))
    )
    (net (code "123") (name "unconnected-(U10-D8-Pad26)") (class "Default")
      (node (ref "U10") (pin "26") (pinfunction "D8_26") (pintype "unspecified"))
    )
    (net (code "124") (name "unconnected-(U10-D9{slash}PWM-Pad27)") (class "Default")
      (node (ref "U10") (pin "27") (pinfunction "D9/PWM_27") (pintype "unspecified"))
    )
    (net (code "125") (name "unconnected-(U10-D10{slash}PWM-Pad28)") (class "Default")
      (node (ref "U10") (pin "28") (pinfunction "D10/PWM_28") (pintype "unspecified"))
    )
    (net (code "126") (name "unconnected-(U10-D11{slash}MOSI-Pad29)") (class "Default")
      (node (ref "U10") (pin "29") (pinfunction "D11/MOSI_29") (pintype "unspecified"))
    )
    (net (code "127") (name "unconnected-(U10-D12{slash}MISO-Pad30)") (class "Default")
      (node (ref "U10") (pin "30") (pinfunction "D12/MISO_30") (pintype "unspecified"))
    )
    (net (code "128") (name "unconnected-(U10-D13-Pad1)") (class "Default")
      (node (ref "U10") (pin "1") (pinfunction "D13_1") (pintype "unspecified"))
    )
    (net (code "129") (name "unconnected-(U10-GND-Pad19)") (class "Default")
      (node (ref "U10") (pin "19") (pinfunction "GND_19") (pintype "unspecified"))
    )
    (net (code "130") (name "unconnected-(U10-RST-Pad13)") (class "Default")
      (node (ref "U10") (pin "13") (pinfunction "RST_13") (pintype "unspecified"))
    )
    (net (code "131") (name "unconnected-(U10-RST-Pad18)") (class "Default")
      (node (ref "U10") (pin "18") (pinfunction "RST_18") (pintype "unspecified"))
    )
    (net (code "132") (name "unconnected-(U10-VIN-Pad15)") (class "Default")
      (node (ref "U10") (pin "15") (pinfunction "VIN_15") (pintype "unspecified"))
    )
    (net (code "133") (name "unconnected-(U11-+3V3-Pad2)") (class "Default")
      (node (ref "U11") (pin "2") (pinfunction "+3V3_2") (pintype "unspecified"))
    )
    (net (code "134") (name "unconnected-(U11-A0{slash}DAC0-Pad4)") (class "Default")
      (node (ref "U11") (pin "4") (pinfunction "A0/DAC0_4") (pintype "unspecified"))
    )
    (net (code "135") (name "unconnected-(U11-A1-Pad5)") (class "Default")
      (node (ref "U11") (pin "5") (pinfunction "A1_5") (pintype "unspecified"))
    )
    (net (code "136") (name "unconnected-(U11-A2-Pad6)") (class "Default")
      (node (ref "U11") (pin "6") (pinfunction "A2_6") (pintype "unspecified"))
    )
    (net (code "137") (name "unconnected-(U11-A3-Pad7)") (class "Default")
      (node (ref "U11") (pin "7") (pinfunction "A3_7") (pintype "unspecified"))
    )
    (net (code "138") (name "unconnected-(U11-A4{slash}SDA-Pad8)") (class "Default")
      (node (ref "U11") (pin "8") (pinfunction "A4/SDA_8") (pintype "unspecified"))
    )
    (net (code "139") (name "unconnected-(U11-A5{slash}SCL-Pad9)") (class "Default")
      (node (ref "U11") (pin "9") (pinfunction "A5/SCL_9") (pintype "unspecified"))
    )
    (net (code "140") (name "unconnected-(U11-A6-Pad10)") (class "Default")
      (node (ref "U11") (pin "10") (pinfunction "A6_10") (pintype "unspecified"))
    )
    (net (code "141") (name "unconnected-(U11-A7-Pad11)") (class "Default")
      (node (ref "U11") (pin "11") (pinfunction "A7_11") (pintype "unspecified"))
    )
    (net (code "142") (name "unconnected-(U11-AREF-Pad3)") (class "Default")
      (node (ref "U11") (pin "3") (pinfunction "AREF_3") (pintype "unspecified"))
    )
    (net (code "143") (name "unconnected-(U11-D2-Pad20)") (class "Default")
      (node (ref "U11") (pin "20") (pinfunction "D2_20") (pintype "unspecified"))
    )
    (net (code "144") (name "unconnected-(U11-D3{slash}PWM-Pad21)") (class "Default")
      (node (ref "U11") (pin "21") (pinfunction "D3/PWM_21") (pintype "unspecified"))
    )
    (net (code "145") (name "unconnected-(U11-D4-Pad22)") (class "Default")
      (node (ref "U11") (pin "22") (pinfunction "D4_22") (pintype "unspecified"))
    )
    (net (code "146") (name "unconnected-(U11-D5{slash}PWM-Pad23)") (class "Default")
      (node (ref "U11") (pin "23") (pinfunction "D5/PWM_23") (pintype "unspecified"))
    )
    (net (code "147") (name "unconnected-(U11-D6{slash}PWM-Pad24)") (class "Default")
      (node (ref "U11") (pin "24") (pinfunction "D6/PWM_24") (pintype "unspecified"))
    )
    (net (code "148") (name "unconnected-(U11-D7-Pad25)") (class "Default")
      (node (ref "U11") (pin "25") (pinfunction "D7_25") (pintype "unspecified"))
    )
    (net (code "149") (name "unconnected-(U11-D8-Pad26)") (class "Default")
      (node (ref "U11") (pin "26") (pinfunction "D8_26") (pintype "unspecified"))
    )
    (net (code "150") (name "unconnected-(U11-D9{slash}PWM-Pad27)") (class "Default")
      (node (ref "U11") (pin "27") (pinfunction "D9/PWM_27") (pintype "unspecified"))
    )
    (net (code "151") (name "unconnected-(U11-D10{slash}PWM-Pad28)") (class "Default")
      (node (ref "U11") (pin "28") (pinfunction "D10/PWM_28") (pintype "unspecified"))
    )
    (net (code "152") (name "unconnected-(U11-D11{slash}MOSI-Pad29)") (class "Default")
      (node (ref "U11") (pin "29") (pinfunction "D11/MOSI_29") (pintype "unspecified"))
    )
    (net (code "153") (name "unconnected-(U11-GND-Pad14)") (class "Default")
      (node (ref "U11") (pin "14") (pinfunction "GND_14") (pintype "unspecified"))
    )
    (net (code "154") (name "unconnected-(U11-RST-Pad13)") (class "Default")
      (node (ref "U11") (pin "13") (pinfunction "RST_13") (pintype "unspecified"))
    )
    (net (code "155") (name "unconnected-(U11-RST-Pad18)") (class "Default")
      (node (ref "U11") (pin "18") (pinfunction "RST_18") (pintype "unspecified"))
    )
    (net (code "156") (name "unconnected-(U11-RX-Pad17)") (class "Default")
      (node (ref "U11") (pin "17") (pinfunction "RX_17") (pintype "unspecified"))
    )
    (net (code "157") (name "unconnected-(U11-TX-Pad16)") (class "Default")
      (node (ref "U11") (pin "16") (pinfunction "TX_16") (pintype "unspecified"))
    )
  )
)
